# Sheet1.net
KiCad netlist of a schematic drawn in Altium Designer
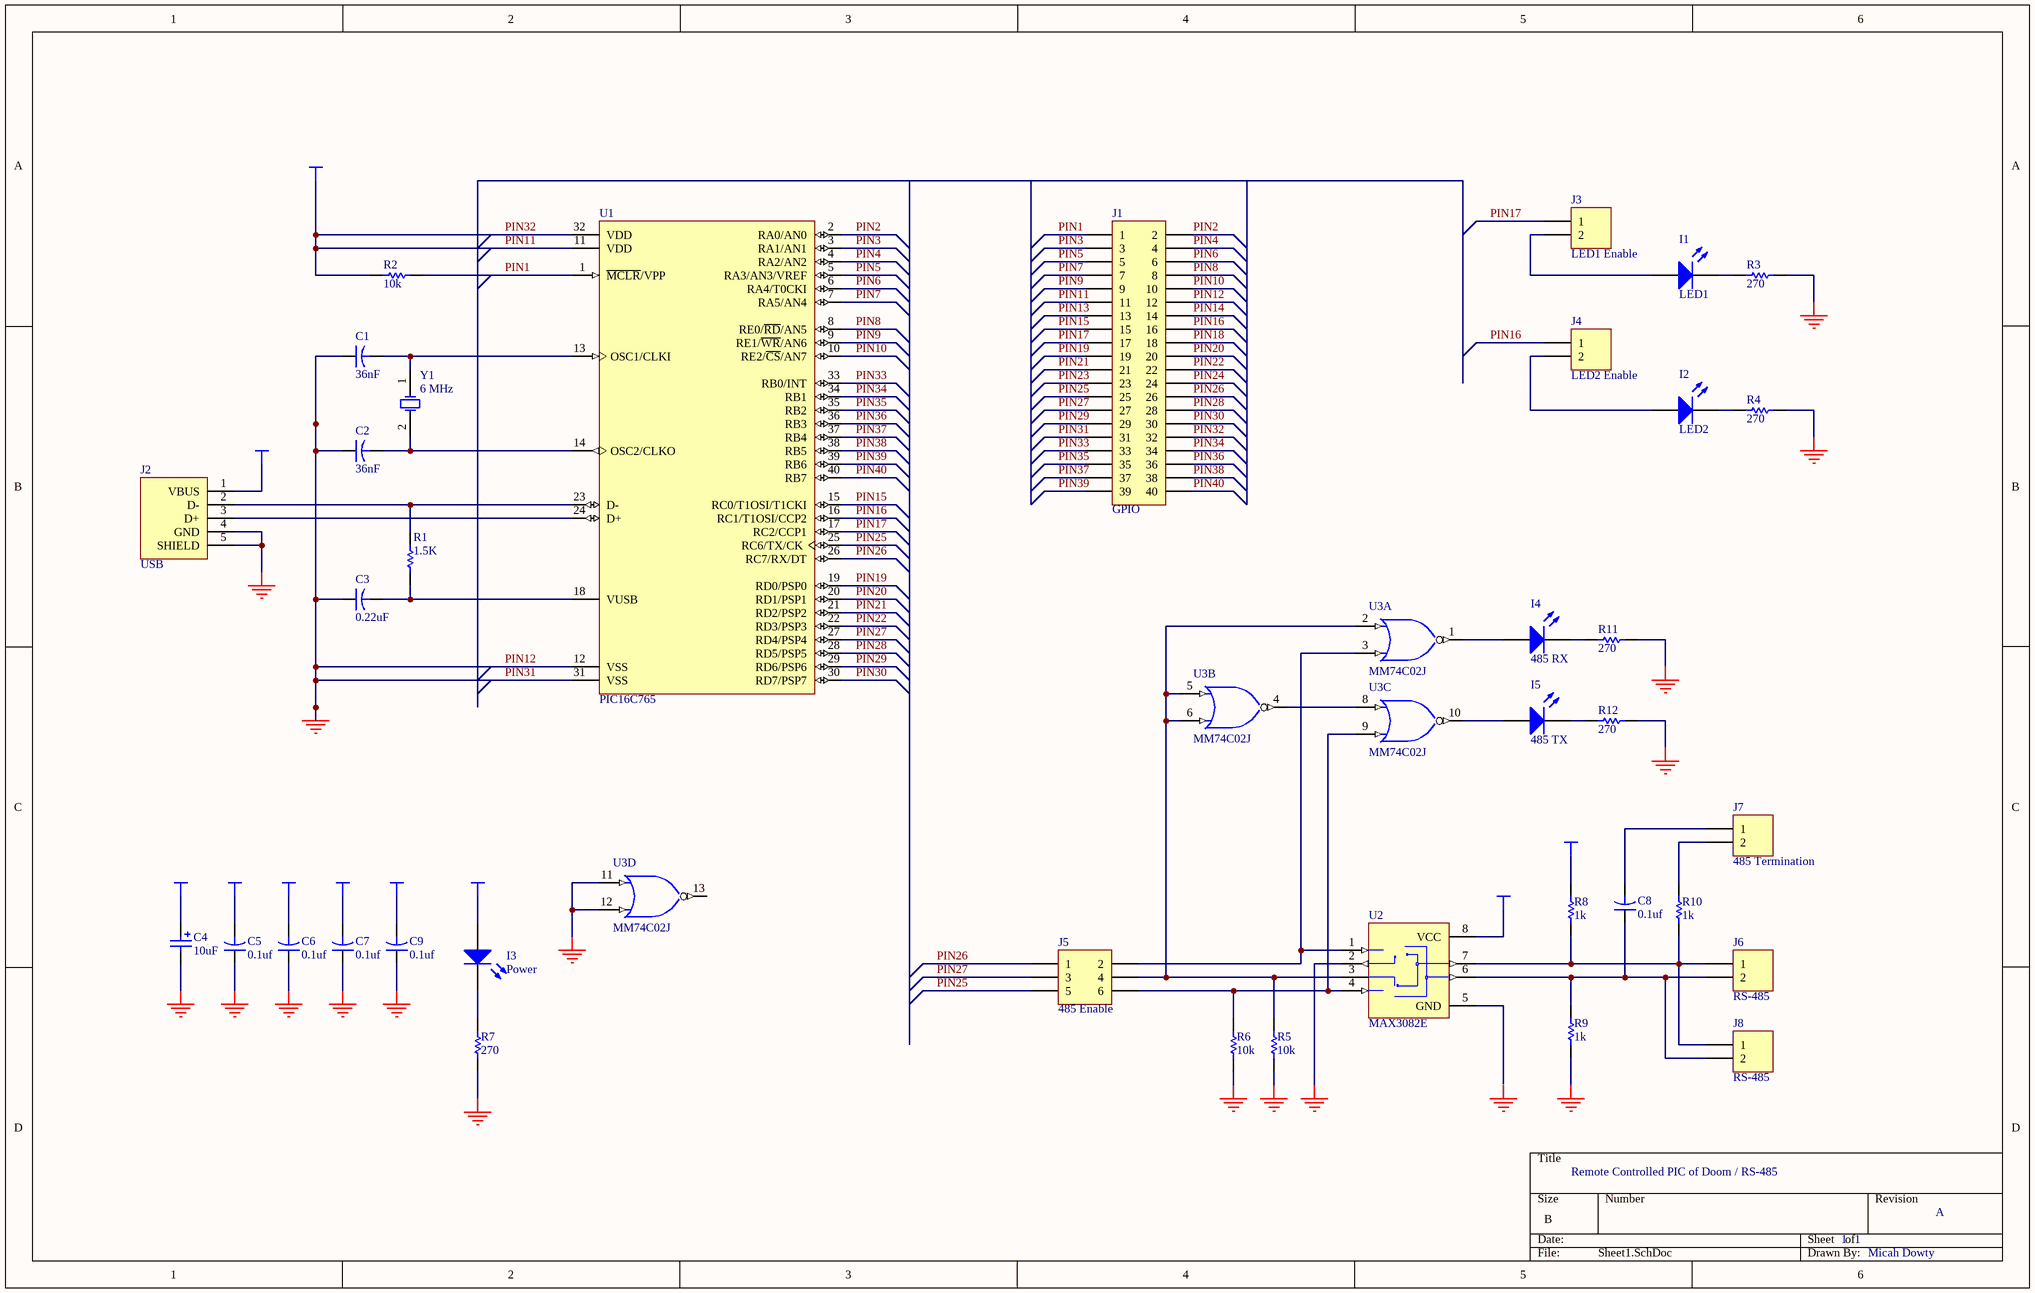
[diagram p0: Sheet1.SchDoc]

(export (version "E")
  (design (tool "Eeschema 10.0.6"))
  (components
    (comp (ref "C1")
      (value "Cap2")
      (footprint "CAPR5-4X5")
      (description "Capacitor")
      (fields
        (field (name "MANUFACTURER") "Generic Components")
        (field (name "ALTIUM_VALUE") "36nF")
        (field (name "PUBLISHER") "Altium Limited")
      )
      (libsource (lib "Miscellaneous Devices") (part "Cap2"))
    )
    (comp (ref "C2")
      (value "Cap2")
      (footprint "CAPR5-4X5")
      (description "Capacitor")
      (fields
        (field (name "MANUFACTURER") "Generic Components")
        (field (name "ALTIUM_VALUE") "36nF")
        (field (name "PUBLISHER") "Altium Limited")
      )
      (libsource (lib "Miscellaneous Devices") (part "Cap2"))
    )
    (comp (ref "C3")
      (value "0.22uF")
      (footprint "CAPR5-4X5")
      (description "Capacitor")
      (fields (field (name "MANUFACTURER") "Generic Components") (field (name "PUBLISHER") "Altium Limited"))
      (libsource (lib "Miscellaneous Devices") (part "Cap2"))
    )
    (comp (ref "C4")
      (value "10uF")
      (footprint "CAP-EE-1")
      (description "Polarized Capacitor (Radial)")
      (fields (field (name "MANUFACTURER") "Generic Components") (field (name "PUBLISHER") "Altium Limited"))
      (libsource (lib "Miscellaneous Devices") (part "Cap Pol1"))
    )
    (comp (ref "C5")
      (value "0.1uf")
      (footprint "CAPR5-4X5")
      (description "Capacitor")
      (fields (field (name "MANUFACTURER") "Generic Components") (field (name "PUBLISHER") "Altium Limited"))
      (libsource (lib "Miscellaneous Devices") (part "Cap2"))
    )
    (comp (ref "C6")
      (value "0.1uf")
      (footprint "CAPR5-4X5")
      (description "Capacitor")
      (fields (field (name "MANUFACTURER") "Generic Components") (field (name "PUBLISHER") "Altium Limited"))
      (libsource (lib "Miscellaneous Devices") (part "Cap2"))
    )
    (comp (ref "C7")
      (value "0.1uf")
      (footprint "CAPR5-4X5")
      (description "Capacitor")
      (fields (field (name "MANUFACTURER") "Generic Components") (field (name "PUBLISHER") "Altium Limited"))
      (libsource (lib "Miscellaneous Devices") (part "Cap2"))
    )
    (comp (ref "C8")
      (value "0.1uf")
      (footprint "CAPR5-4X5")
      (description "Capacitor")
      (fields (field (name "MANUFACTURER") "Generic Components") (field (name "PUBLISHER") "Altium Limited"))
      (libsource (lib "Miscellaneous Devices") (part "Cap2"))
    )
    (comp (ref "C9")
      (value "0.1uf")
      (footprint "CAPR5-4X5")
      (description "Capacitor")
      (fields (field (name "MANUFACTURER") "Generic Components") (field (name "PUBLISHER") "Altium Limited"))
      (libsource (lib "Miscellaneous Devices") (part "Cap2"))
    )
    (comp (ref "I1")
      (value "LED1")
      (footprint "LED-1")
      (description "Typical RED GaAs LED")
      (fields (field (name "MANUFACTURER") "Generic Components") (field (name "PUBLISHER") "Altium Limited"))
      (libsource (lib "Miscellaneous Devices") (part "LED1"))
    )
    (comp (ref "I2")
      (value "LED2")
      (footprint "LED-1")
      (description "Typical RED GaAs LED")
      (fields (field (name "MANUFACTURER") "Generic Components") (field (name "PUBLISHER") "Altium Limited"))
      (libsource (lib "Miscellaneous Devices") (part "LED1"))
    )
    (comp (ref "I3")
      (value "Power")
      (footprint "LED-1")
      (description "Typical RED GaAs LED")
      (fields (field (name "MANUFACTURER") "Generic Components") (field (name "PUBLISHER") "Altium Limited"))
      (libsource (lib "Miscellaneous Devices") (part "LED1"))
    )
    (comp (ref "I4")
      (value "485 RX")
      (footprint "LED-1")
      (description "Typical RED GaAs LED")
      (fields (field (name "MANUFACTURER") "Generic Components") (field (name "PUBLISHER") "Altium Limited"))
      (libsource (lib "Miscellaneous Devices") (part "LED1"))
    )
    (comp (ref "I5")
      (value "485 TX")
      (footprint "LED-1")
      (description "Typical RED GaAs LED")
      (fields (field (name "MANUFACTURER") "Generic Components") (field (name "PUBLISHER") "Altium Limited"))
      (libsource (lib "Miscellaneous Devices") (part "LED1"))
    )
    (comp (ref "J1")
      (value "GPIO")
      (footprint "HR40")
      (description "Header, 20-Pin, Dual row")
      (fields (field (name "MANUFACTURER") "Generic Components") (field (name "PUBLISHER") "Altium Limited"))
      (libsource (lib "Miscellaneous Connectors") (part "MHDR2X20"))
    )
    (comp (ref "J2")
      (value "USB")
      (footprint "USB-TYPEB")
      (description "Header, 4-Pin")
      (fields (field (name "MANUFACTURER") "Generic Components") (field (name "PUBLISHER") "Altium Limited"))
      (libsource (lib "parts") (part "USB Type B"))
    )
    (comp (ref "J3")
      (value "LED1 Enable")
      (footprint "HDR1X2")
      (description "Header, 2-Pin")
      (fields (field (name "MANUFACTURER") "Generic Components") (field (name "PUBLISHER") "Altium Limited"))
      (libsource (lib "Miscellaneous Connectors") (part "MHDR1X2"))
    )
    (comp (ref "J4")
      (value "LED2 Enable")
      (footprint "HDR1X2")
      (description "Header, 2-Pin")
      (fields (field (name "MANUFACTURER") "Generic Components") (field (name "PUBLISHER") "Altium Limited"))
      (libsource (lib "Miscellaneous Connectors") (part "MHDR1X2"))
    )
    (comp (ref "J5")
      (value "485 Enable")
      (footprint "HDR2X3_NOTEXT")
      (description "Header, 3-Pin, Dual row")
      (fields (field (name "MANUFACTURER") "Generic Components") (field (name "PUBLISHER") "Altium Limited"))
      (libsource (lib "Miscellaneous Connectors") (part "MHDR2X3"))
    )
    (comp (ref "J6")
      (value "RS-485")
      (footprint "RS485J")
      (description "Header, 2-Pin")
      (fields (field (name "MANUFACTURER") "Generic Components") (field (name "PUBLISHER") "Altium Limited"))
      (libsource (lib "Miscellaneous Connectors") (part "MHDR1X2"))
    )
    (comp (ref "J7")
      (value "485 Termination")
      (footprint "HDR1X2")
      (description "Header, 2-Pin")
      (fields (field (name "MANUFACTURER") "Generic Components") (field (name "PUBLISHER") "Altium Limited"))
      (libsource (lib "Miscellaneous Connectors") (part "MHDR1X2"))
    )
    (comp (ref "J8")
      (value "RS-485")
      (footprint "RS485J")
      (description "Header, 2-Pin")
      (fields (field (name "MANUFACTURER") "Generic Components") (field (name "PUBLISHER") "Altium Limited"))
      (libsource (lib "Miscellaneous Connectors") (part "MHDR1X2"))
    )
    (comp (ref "R1")
      (value "Res1")
      (footprint "AXIAL-0.3")
      (description "Resistor")
      (fields
        (field (name "MANUFACTURER") "Generic Components")
        (field (name "ALTIUM_VALUE") "1.5K")
        (field (name "PUBLISHER") "Altium Limited")
      )
      (libsource (lib "Miscellaneous Devices") (part "Res1"))
    )
    (comp (ref "R2")
      (value "Res1")
      (footprint "AXIAL-0.3")
      (description "Resistor")
      (fields
        (field (name "MANUFACTURER") "Generic Components")
        (field (name "ALTIUM_VALUE") "10k")
        (field (name "PUBLISHER") "Altium Limited")
      )
      (libsource (lib "Miscellaneous Devices") (part "Res1"))
    )
    (comp (ref "R3")
      (value "Res1")
      (footprint "AXIAL-0.3")
      (description "Resistor")
      (fields
        (field (name "MANUFACTURER") "Generic Components")
        (field (name "ALTIUM_VALUE") "270")
        (field (name "PUBLISHER") "Altium Limited")
      )
      (libsource (lib "Miscellaneous Devices") (part "Res1"))
    )
    (comp (ref "R4")
      (value "Res1")
      (footprint "AXIAL-0.3")
      (description "Resistor")
      (fields
        (field (name "MANUFACTURER") "Generic Components")
        (field (name "ALTIUM_VALUE") "270")
        (field (name "PUBLISHER") "Altium Limited")
      )
      (libsource (lib "Miscellaneous Devices") (part "Res1"))
    )
    (comp (ref "R5")
      (value "Res1")
      (footprint "AXIAL-0.3")
      (description "Resistor")
      (fields
        (field (name "MANUFACTURER") "Generic Components")
        (field (name "ALTIUM_VALUE") "10k")
        (field (name "PUBLISHER") "Altium Limited")
      )
      (libsource (lib "Miscellaneous Devices") (part "Res1"))
    )
    (comp (ref "R6")
      (value "Res1")
      (footprint "AXIAL-0.3")
      (description "Resistor")
      (fields
        (field (name "MANUFACTURER") "Generic Components")
        (field (name "ALTIUM_VALUE") "10k")
        (field (name "PUBLISHER") "Altium Limited")
      )
      (libsource (lib "Miscellaneous Devices") (part "Res1"))
    )
    (comp (ref "R7")
      (value "270")
      (footprint "AXIAL-0.3")
      (description "Resistor")
      (fields (field (name "MANUFACTURER") "Generic Components") (field (name "PUBLISHER") "Altium Limited"))
      (libsource (lib "Miscellaneous Devices") (part "Res1"))
    )
    (comp (ref "R8")
      (value "1k")
      (footprint "AXIAL-0.3")
      (description "Resistor")
      (fields (field (name "MANUFACTURER") "Generic Components") (field (name "PUBLISHER") "Altium Limited"))
      (libsource (lib "Miscellaneous Devices") (part "Res1"))
    )
    (comp (ref "R9")
      (value "1k")
      (footprint "AXIAL-0.3")
      (description "Resistor")
      (fields (field (name "MANUFACTURER") "Generic Components") (field (name "PUBLISHER") "Altium Limited"))
      (libsource (lib "Miscellaneous Devices") (part "Res1"))
    )
    (comp (ref "R10")
      (value "1k")
      (footprint "AXIAL-0.3")
      (description "Resistor")
      (fields (field (name "MANUFACTURER") "Generic Components") (field (name "PUBLISHER") "Altium Limited"))
      (libsource (lib "Miscellaneous Devices") (part "Res1"))
    )
    (comp (ref "R11")
      (value "270")
      (footprint "AXIAL-0.3")
      (description "Resistor")
      (fields (field (name "MANUFACTURER") "Generic Components") (field (name "PUBLISHER") "Altium Limited"))
      (libsource (lib "Miscellaneous Devices") (part "Res1"))
    )
    (comp (ref "R12")
      (value "270")
      (footprint "AXIAL-0.3")
      (description "Resistor")
      (fields (field (name "MANUFACTURER") "Generic Components") (field (name "PUBLISHER") "Altium Limited"))
      (libsource (lib "Miscellaneous Devices") (part "Res1"))
    )
    (comp (ref "U1")
      (value "PIC16C765")
      (footprint "DIP-40")
      (description "EPROM-Based 8-Bit CMOS Microcontroller with USB")
      (fields (field (name "MANUFACTURER") "Microchip"))
      (libsource (lib "parts") (part "PIC16C765"))
    )
    (comp (ref "U2")
      (value "MAX3082E")
      (footprint "DIP-8")
      (description "+5V-Powered, RS-485 Driver/Receiver")
      (fields (field (name "MANUFACTURER") "Maxim") (field (name "PUBLISHER") "Micah Dowty"))
      (libsource (lib "parts") (part "MAX3082E"))
    )
    (comp (ref "U3")
      (value "MM74C02J")
      (footprint "DIP-14")
      (description "Quad 2-Input NOR Gate")
      (fields
        (field (name "MANUFACTURER") "National Semiconductor")
        (field (name "PUBLISHER") "Altium Limited")
      )
      (libsource (lib "NSC Logic Gate") (part "MM74C02J"))
    )
    (comp (ref "Y1")
      (value "6 MHz")
      (footprint "BCY-W2/E4.7")
      (description "Crystal Oscillator")
      (fields (field (name "MANUFACTURER") "Generic Components") (field (name "PUBLISHER") "Altium Limited"))
      (libsource (lib "Miscellaneous Devices") (part "XTAL"))
    )
  )
  (nets
    (net (code "1") (name "/PIN1") (class "Default")
      (node (ref "J1") (pin "1") (pinfunction "1_1") (pintype "passive"))
      (node (ref "R2") (pin "1") (pinfunction "1_1") (pintype "passive"))
      (node (ref "U1") (pin "1") (pinfunction "~{MCLR}/VPP_1") (pintype "input"))
    )
    (net (code "2") (name "/PIN2") (class "Default")
      (node (ref "J1") (pin "2") (pinfunction "2_2") (pintype "passive"))
      (node (ref "U1") (pin "2") (pinfunction "RA0/AN0_2") (pintype "bidirectional"))
    )
    (net (code "3") (name "/PIN3") (class "Default")
      (node (ref "J1") (pin "3") (pinfunction "3_3") (pintype "passive"))
      (node (ref "U1") (pin "3") (pinfunction "RA1/AN1_3") (pintype "bidirectional"))
    )
    (net (code "4") (name "/PIN4") (class "Default")
      (node (ref "J1") (pin "4") (pinfunction "4_4") (pintype "passive"))
      (node (ref "U1") (pin "4") (pinfunction "RA2/AN2_4") (pintype "bidirectional"))
    )
    (net (code "5") (name "/PIN5") (class "Default")
      (node (ref "J1") (pin "5") (pinfunction "5_5") (pintype "passive"))
      (node (ref "U1") (pin "5") (pinfunction "RA3/AN3/VREF_5") (pintype "bidirectional"))
    )
    (net (code "6") (name "/PIN6") (class "Default")
      (node (ref "J1") (pin "6") (pinfunction "6_6") (pintype "passive"))
      (node (ref "U1") (pin "6") (pinfunction "RA4/T0CKI_6") (pintype "bidirectional"))
    )
    (net (code "7") (name "/PIN7") (class "Default")
      (node (ref "J1") (pin "7") (pinfunction "7_7") (pintype "passive"))
      (node (ref "U1") (pin "7") (pinfunction "RA5/AN4_7") (pintype "bidirectional"))
    )
    (net (code "8") (name "/PIN8") (class "Default")
      (node (ref "J1") (pin "8") (pinfunction "8_8") (pintype "passive"))
      (node (ref "U1") (pin "8") (pinfunction "RE0/~{RD}/AN5_8") (pintype "bidirectional"))
    )
    (net (code "9") (name "/PIN9") (class "Default")
      (node (ref "J1") (pin "9") (pinfunction "9_9") (pintype "passive"))
      (node (ref "U1") (pin "9") (pinfunction "RE1/~{WR}/AN6_9") (pintype "bidirectional"))
    )
    (net (code "10") (name "/PIN10") (class "Default")
      (node (ref "J1") (pin "10") (pinfunction "10_10") (pintype "passive"))
      (node (ref "U1") (pin "10") (pinfunction "RE2/~{CS}/AN7_10") (pintype "bidirectional"))
    )
    (net (code "11") (name "/PIN13") (class "Default")
      (node (ref "J1") (pin "13") (pinfunction "13_13") (pintype "passive"))
    )
    (net (code "12") (name "/PIN14") (class "Default")
      (node (ref "J1") (pin "14") (pinfunction "14_14") (pintype "passive"))
    )
    (net (code "13") (name "/PIN15") (class "Default")
      (node (ref "J1") (pin "15") (pinfunction "15_15") (pintype "passive"))
      (node (ref "U1") (pin "15") (pinfunction "RC0/T1OSI/T1CKI_15") (pintype "bidirectional"))
    )
    (net (code "14") (name "/PIN16") (class "Default")
      (node (ref "J1") (pin "16") (pinfunction "16_16") (pintype "passive"))
      (node (ref "J4") (pin "1") (pinfunction "1_1") (pintype "passive"))
      (node (ref "U1") (pin "16") (pinfunction "RC1/T1OSI/CCP2_16") (pintype "bidirectional"))
    )
    (net (code "15") (name "/PIN17") (class "Default")
      (node (ref "J1") (pin "17") (pinfunction "17_17") (pintype "passive"))
      (node (ref "J3") (pin "1") (pinfunction "1_1") (pintype "passive"))
      (node (ref "U1") (pin "17") (pinfunction "RC2/CCP1_17") (pintype "bidirectional"))
    )
    (net (code "16") (name "/PIN18") (class "Default")
      (node (ref "J1") (pin "18") (pinfunction "18_18") (pintype "passive"))
    )
    (net (code "17") (name "/PIN19") (class "Default")
      (node (ref "J1") (pin "19") (pinfunction "19_19") (pintype "passive"))
      (node (ref "U1") (pin "19") (pinfunction "RD0/PSP0_19") (pintype "bidirectional"))
    )
    (net (code "18") (name "/PIN20") (class "Default")
      (node (ref "J1") (pin "20") (pinfunction "20_20") (pintype "passive"))
      (node (ref "U1") (pin "20") (pinfunction "RD1/PSP1_20") (pintype "bidirectional"))
    )
    (net (code "19") (name "/PIN21") (class "Default")
      (node (ref "J1") (pin "21") (pinfunction "21_21") (pintype "passive"))
      (node (ref "U1") (pin "21") (pinfunction "RD2/PSP2_21") (pintype "bidirectional"))
    )
    (net (code "20") (name "/PIN22") (class "Default")
      (node (ref "J1") (pin "22") (pinfunction "22_22") (pintype "passive"))
      (node (ref "U1") (pin "22") (pinfunction "RD3/PSP3_22") (pintype "bidirectional"))
    )
    (net (code "21") (name "/PIN23") (class "Default")
      (node (ref "J1") (pin "23") (pinfunction "23_23") (pintype "passive"))
    )
    (net (code "22") (name "/PIN24") (class "Default")
      (node (ref "J1") (pin "24") (pinfunction "24_24") (pintype "passive"))
    )
    (net (code "23") (name "/PIN25") (class "Default")
      (node (ref "J1") (pin "25") (pinfunction "25_25") (pintype "passive"))
      (node (ref "J5") (pin "5") (pinfunction "5_5") (pintype "passive"))
      (node (ref "U1") (pin "25") (pinfunction "RC6/TX/CK_25") (pintype "bidirectional"))
    )
    (net (code "24") (name "/PIN26") (class "Default")
      (node (ref "J1") (pin "26") (pinfunction "26_26") (pintype "passive"))
      (node (ref "J5") (pin "1") (pinfunction "1_1") (pintype "passive"))
      (node (ref "U1") (pin "26") (pinfunction "RC7/RX/DT_26") (pintype "bidirectional"))
    )
    (net (code "25") (name "/PIN27") (class "Default")
      (node (ref "J1") (pin "27") (pinfunction "27_27") (pintype "passive"))
      (node (ref "J5") (pin "3") (pinfunction "3_3") (pintype "passive"))
      (node (ref "U1") (pin "27") (pinfunction "RD4/PSP4_27") (pintype "bidirectional"))
    )
    (net (code "26") (name "/PIN28") (class "Default")
      (node (ref "J1") (pin "28") (pinfunction "28_28") (pintype "passive"))
      (node (ref "U1") (pin "28") (pinfunction "RD5/PSP5_28") (pintype "bidirectional"))
    )
    (net (code "27") (name "/PIN29") (class "Default")
      (node (ref "J1") (pin "29") (pinfunction "29_29") (pintype "passive"))
      (node (ref "U1") (pin "29") (pinfunction "RD6/PSP6_29") (pintype "bidirectional"))
    )
    (net (code "28") (name "/PIN30") (class "Default")
      (node (ref "J1") (pin "30") (pinfunction "30_30") (pintype "passive"))
      (node (ref "U1") (pin "30") (pinfunction "RD7/PSP7_30") (pintype "bidirectional"))
    )
    (net (code "29") (name "/PIN33") (class "Default")
      (node (ref "J1") (pin "33") (pinfunction "33_33") (pintype "passive"))
      (node (ref "U1") (pin "33") (pinfunction "RB0/INT_33") (pintype "bidirectional"))
    )
    (net (code "30") (name "/PIN34") (class "Default")
      (node (ref "J1") (pin "34") (pinfunction "34_34") (pintype "passive"))
      (node (ref "U1") (pin "34") (pinfunction "RB1_34") (pintype "bidirectional"))
    )
    (net (code "31") (name "/PIN35") (class "Default")
      (node (ref "J1") (pin "35") (pinfunction "35_35") (pintype "passive"))
      (node (ref "U1") (pin "35") (pinfunction "RB2_35") (pintype "bidirectional"))
    )
    (net (code "32") (name "/PIN36") (class "Default")
      (node (ref "J1") (pin "36") (pinfunction "36_36") (pintype "passive"))
      (node (ref "U1") (pin "36") (pinfunction "RB3_36") (pintype "bidirectional"))
    )
    (net (code "33") (name "/PIN37") (class "Default")
      (node (ref "J1") (pin "37") (pinfunction "37_37") (pintype "passive"))
      (node (ref "U1") (pin "37") (pinfunction "RB4_37") (pintype "bidirectional"))
    )
    (net (code "34") (name "/PIN38") (class "Default")
      (node (ref "J1") (pin "38") (pinfunction "38_38") (pintype "passive"))
      (node (ref "U1") (pin "38") (pinfunction "RB5_38") (pintype "bidirectional"))
    )
    (net (code "35") (name "/PIN39") (class "Default")
      (node (ref "J1") (pin "39") (pinfunction "39_39") (pintype "passive"))
      (node (ref "U1") (pin "39") (pinfunction "RB6_39") (pintype "bidirectional"))
    )
    (net (code "36") (name "/PIN40") (class "Default")
      (node (ref "J1") (pin "40") (pinfunction "40_40") (pintype "passive"))
      (node (ref "U1") (pin "40") (pinfunction "RB7_40") (pintype "bidirectional"))
    )
    (net (code "37") (name "GND") (class "Default")
      (node (ref "C1") (pin "1") (pinfunction "1_1") (pintype "passive"))
      (node (ref "C2") (pin "1") (pinfunction "1_1") (pintype "passive"))
      (node (ref "C3") (pin "1") (pinfunction "1_1") (pintype "passive"))
      (node (ref "C4") (pin "2") (pinfunction "2_2") (pintype "passive"))
      (node (ref "C5") (pin "1") (pinfunction "1_1") (pintype "passive"))
      (node (ref "C6") (pin "1") (pinfunction "1_1") (pintype "passive"))
      (node (ref "C7") (pin "1") (pinfunction "1_1") (pintype "passive"))
      (node (ref "C9") (pin "1") (pinfunction "1_1") (pintype "passive"))
      (node (ref "J1") (pin "12") (pinfunction "12_12") (pintype "passive"))
      (node (ref "J1") (pin "31") (pinfunction "31_31") (pintype "passive"))
      (node (ref "J2") (pin "4") (pinfunction "GND_4") (pintype "passive"))
      (node (ref "J2") (pin "5") (pinfunction "SHIELD_5") (pintype "power_in"))
      (node (ref "R11") (pin "2") (pinfunction "2_2") (pintype "passive"))
      (node (ref "R12") (pin "2") (pinfunction "2_2") (pintype "passive"))
      (node (ref "R3") (pin "2") (pinfunction "2_2") (pintype "passive"))
      (node (ref "R4") (pin "2") (pinfunction "2_2") (pintype "passive"))
      (node (ref "R5") (pin "1") (pinfunction "1_1") (pintype "passive"))
      (node (ref "R6") (pin "1") (pinfunction "1_1") (pintype "passive"))
      (node (ref "R7") (pin "2") (pinfunction "2_2") (pintype "passive"))
      (node (ref "R9") (pin "2") (pinfunction "2_2") (pintype "passive"))
      (node (ref "U1") (pin "12") (pinfunction "VSS_12") (pintype "power_in"))
      (node (ref "U1") (pin "31") (pinfunction "VSS_31") (pintype "power_in"))
      (node (ref "U2") (pin "2") (pinfunction "~{RE}_2") (pintype "output"))
      (node (ref "U3") (pin "11") (pinfunction "A_11") (pintype "input"))
      (node (ref "U3") (pin "12") (pinfunction "B_12") (pintype "input"))
      (node (ref "U3") (pin "7") (pinfunction "GND_7") (pintype "power_in"))
    )
    (net (code "38") (name "Net-(C8-Pad2)") (class "Default")
      (node (ref "C8") (pin "2") (pinfunction "2_2") (pintype "passive"))
      (node (ref "J7") (pin "1") (pinfunction "1_1") (pintype "passive"))
    )
    (net (code "39") (name "Net-(I1-A)") (class "Default")
      (node (ref "I1") (pin "1") (pinfunction "A_1") (pintype "passive"))
      (node (ref "J3") (pin "2") (pinfunction "2_2") (pintype "passive"))
    )
    (net (code "40") (name "Net-(I1-K)") (class "Default")
      (node (ref "I1") (pin "2") (pinfunction "K_2") (pintype "passive"))
      (node (ref "R3") (pin "1") (pinfunction "1_1") (pintype "passive"))
    )
    (net (code "41") (name "Net-(I2-A)") (class "Default")
      (node (ref "I2") (pin "1") (pinfunction "A_1") (pintype "passive"))
      (node (ref "J4") (pin "2") (pinfunction "2_2") (pintype "passive"))
    )
    (net (code "42") (name "Net-(I2-K)") (class "Default")
      (node (ref "I2") (pin "2") (pinfunction "K_2") (pintype "passive"))
      (node (ref "R4") (pin "1") (pinfunction "1_1") (pintype "passive"))
    )
    (net (code "43") (name "Net-(I3-K)") (class "Default")
      (node (ref "I3") (pin "2") (pinfunction "K_2") (pintype "passive"))
      (node (ref "R7") (pin "1") (pinfunction "1_1") (pintype "passive"))
    )
    (net (code "44") (name "Net-(I4-A)") (class "Default")
      (node (ref "I4") (pin "1") (pinfunction "A_1") (pintype "passive"))
      (node (ref "U3") (pin "1") (pinfunction "Y_1") (pintype "output"))
    )
    (net (code "45") (name "Net-(I4-K)") (class "Default")
      (node (ref "I4") (pin "2") (pinfunction "K_2") (pintype "passive"))
      (node (ref "R11") (pin "1") (pinfunction "1_1") (pintype "passive"))
    )
    (net (code "46") (name "Net-(I5-A)") (class "Default")
      (node (ref "I5") (pin "1") (pinfunction "A_1") (pintype "passive"))
      (node (ref "U3") (pin "10") (pinfunction "Y_10") (pintype "output"))
    )
    (net (code "47") (name "Net-(I5-K)") (class "Default")
      (node (ref "I5") (pin "2") (pinfunction "K_2") (pintype "passive"))
      (node (ref "R12") (pin "1") (pinfunction "1_1") (pintype "passive"))
    )
    (net (code "48") (name "Net-(J2-D+)") (class "Default")
      (node (ref "J2") (pin "3") (pinfunction "D+_3") (pintype "passive"))
      (node (ref "U1") (pin "24") (pinfunction "D+_24") (pintype "bidirectional"))
    )
    (net (code "49") (name "Net-(J2-D-)") (class "Default")
      (node (ref "J2") (pin "2") (pinfunction "D-_2") (pintype "passive"))
      (node (ref "R1") (pin "2") (pinfunction "2_2") (pintype "passive"))
      (node (ref "U1") (pin "23") (pinfunction "D-_23") (pintype "bidirectional"))
    )
    (net (code "50") (name "Net-(J7-Pad2)") (class "Default")
      (node (ref "J7") (pin "2") (pinfunction "2_2") (pintype "passive"))
      (node (ref "R10") (pin "1") (pinfunction "1_1") (pintype "passive"))
    )
    (net (code "51") (name "Net-(U1-OSC1{slash}CLKI)") (class "Default")
      (node (ref "C1") (pin "2") (pinfunction "2_2") (pintype "passive"))
      (node (ref "U1") (pin "13") (pinfunction "OSC1/CLKI_13") (pintype "input"))
      (node (ref "Y1") (pin "1") (pinfunction "OSC1_1") (pintype "passive"))
    )
    (net (code "52") (name "Net-(U1-OSC2{slash}CLKO)") (class "Default")
      (node (ref "C2") (pin "2") (pinfunction "2_2") (pintype "passive"))
      (node (ref "U1") (pin "14") (pinfunction "OSC2/CLKO_14") (pintype "output"))
      (node (ref "Y1") (pin "2") (pinfunction "OSC2_2") (pintype "passive"))
    )
    (net (code "53") (name "Net-(U1-VUSB)") (class "Default")
      (node (ref "C3") (pin "2") (pinfunction "2_2") (pintype "passive"))
      (node (ref "R1") (pin "1") (pinfunction "1_1") (pintype "passive"))
      (node (ref "U1") (pin "18") (pinfunction "VUSB_18") (pintype "power_in"))
    )
    (net (code "54") (name "Net-(U2-DE)") (class "Default")
      (node (ref "J5") (pin "4") (pinfunction "4_4") (pintype "passive"))
      (node (ref "R5") (pin "2") (pinfunction "2_2") (pintype "passive"))
      (node (ref "U2") (pin "3") (pinfunction "DE_3") (pintype "passive"))
      (node (ref "U3") (pin "2") (pinfunction "A_2") (pintype "input"))
      (node (ref "U3") (pin "5") (pinfunction "A_5") (pintype "input"))
      (node (ref "U3") (pin "6") (pinfunction "B_6") (pintype "input"))
    )
    (net (code "55") (name "Net-(U2-DI)") (class "Default")
      (node (ref "J5") (pin "6") (pinfunction "6_6") (pintype "passive"))
      (node (ref "R6") (pin "2") (pinfunction "2_2") (pintype "passive"))
      (node (ref "U2") (pin "4") (pinfunction "DI_4") (pintype "input"))
      (node (ref "U3") (pin "9") (pinfunction "B_9") (pintype "input"))
    )
    (net (code "56") (name "Net-(U2-RO)") (class "Default")
      (node (ref "J5") (pin "2") (pinfunction "2_2") (pintype "passive"))
      (node (ref "U2") (pin "1") (pinfunction "RO_1") (pintype "input"))
      (node (ref "U3") (pin "3") (pinfunction "B_3") (pintype "input"))
    )
    (net (code "57") (name "Net-(U2-T1OUT)") (class "Default")
      (node (ref "J6") (pin "1") (pinfunction "1_1") (pintype "passive"))
      (node (ref "J8") (pin "1") (pinfunction "1_1") (pintype "passive"))
      (node (ref "R10") (pin "2") (pinfunction "2_2") (pintype "passive"))
      (node (ref "R8") (pin "2") (pinfunction "2_2") (pintype "passive"))
      (node (ref "U2") (pin "7") (pinfunction "T1OUT_7") (pintype "output"))
    )
    (net (code "58") (name "Net-(U2-T2OUT)") (class "Default")
      (node (ref "C8") (pin "1") (pinfunction "1_1") (pintype "passive"))
      (node (ref "J6") (pin "2") (pinfunction "2_2") (pintype "passive"))
      (node (ref "J8") (pin "2") (pinfunction "2_2") (pintype "passive"))
      (node (ref "R9") (pin "1") (pinfunction "1_1") (pintype "passive"))
      (node (ref "U2") (pin "6") (pinfunction "T2OUT_6") (pintype "output"))
    )
    (net (code "59") (name "Net-(U3B-Y)") (class "Default")
      (node (ref "U3") (pin "4") (pinfunction "Y_4") (pintype "output"))
      (node (ref "U3") (pin "8") (pinfunction "A_8") (pintype "input"))
    )
    (net (code "60") (name "VCC") (class "Default")
      (node (ref "C4") (pin "1") (pinfunction "1_1") (pintype "passive"))
      (node (ref "C5") (pin "2") (pinfunction "2_2") (pintype "passive"))
      (node (ref "C6") (pin "2") (pinfunction "2_2") (pintype "passive"))
      (node (ref "C7") (pin "2") (pinfunction "2_2") (pintype "passive"))
      (node (ref "C9") (pin "2") (pinfunction "2_2") (pintype "passive"))
      (node (ref "I3") (pin "1") (pinfunction "A_1") (pintype "passive"))
      (node (ref "J1") (pin "11") (pinfunction "11_11") (pintype "passive"))
      (node (ref "J1") (pin "32") (pinfunction "32_32") (pintype "passive"))
      (node (ref "J2") (pin "1") (pinfunction "VBUS_1") (pintype "passive"))
      (node (ref "R2") (pin "2") (pinfunction "2_2") (pintype "passive"))
      (node (ref "R8") (pin "1") (pinfunction "1_1") (pintype "passive"))
      (node (ref "U1") (pin "11") (pinfunction "VDD_11") (pintype "power_in"))
      (node (ref "U1") (pin "32") (pinfunction "VDD_32") (pintype "power_in"))
      (node (ref "U2") (pin "8") (pinfunction "VCC_8") (pintype "power_in"))
      (node (ref "U3") (pin "14") (pinfunction "VCC_14") (pintype "power_in"))
    )
    (net (code "61") (name "unconnected-(U2-GND-Pad5)") (class "Default")
      (node (ref "U2") (pin "5") (pinfunction "GND_5") (pintype "power_in"))
    )
    (net (code "62") (name "unconnected-(U3D-Y-Pad13)") (class "Default")
      (node (ref "U3") (pin "13") (pinfunction "Y_13") (pintype "output"))
    )
  )
)
